# LPS25H_breakout.net
KiCad netlist of a schematic drawn in EAGLE
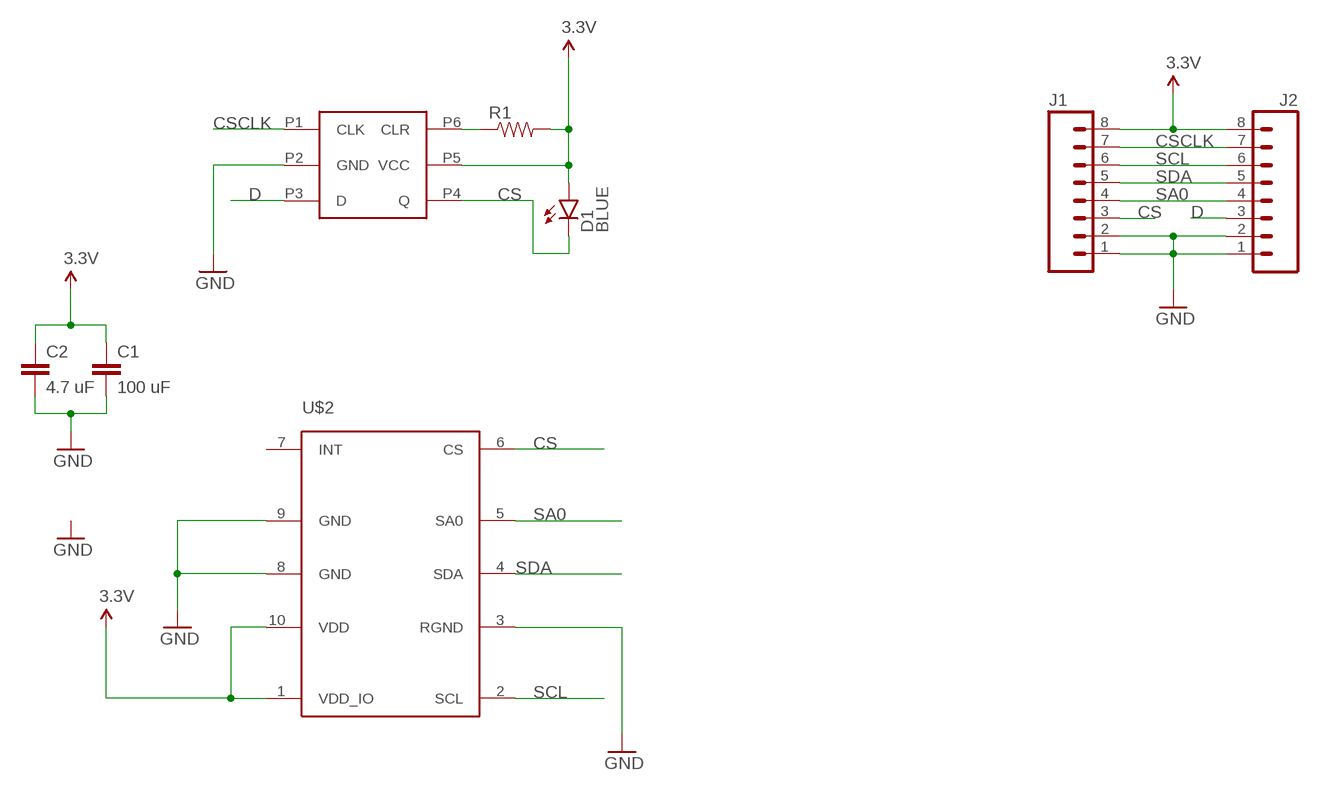
[diagram p0: schematic, sheet 1]

(export (version "E")
  (design (tool "Eeschema 10.0.6"))
  (components
    (comp (ref "C1")
      (value "100 uF")
      (footprint "eagle-import:0603-CAP")
      (libsource (lib "eagle-import") (part "CAP0603-CAP"))
    )
    (comp (ref "C2")
      (value "4.7 uF")
      (footprint "eagle-import:0603-CAP")
      (libsource (lib "eagle-import") (part "CAP0603-CAP"))
    )
    (comp (ref "D1")
      (value "BLUE")
      (footprint "eagle-import:LED-0603")
      (libsource (lib "eagle-import") (part "LED-BLUE0603"))
    )
    (comp (ref "J1")
      (value "M08BM08B-SRSS-TB")
      (footprint "eagle-import:BM08B-SRSS-TB")
      (libsource (lib "eagle-import") (part "M08BM08B-SRSS-TB"))
    )
    (comp (ref "J2")
      (value "M08BM08B-SRSS-TB")
      (footprint "eagle-import:BM08B-SRSS-TB")
      (libsource (lib "eagle-import") (part "M08BM08B-SRSS-TB"))
    )
    (comp (ref "R1")
      (value "RESISTOR0603-RES")
      (footprint "eagle-import:0603-RES")
      (libsource (lib "eagle-import") (part "RESISTOR0603-RES"))
    )
    (comp (ref "U$1")
      (value "SN74LVC1G175")
      (footprint "eagle-import:SN74LVC1G175")
      (libsource (lib "eagle-import") (part "SN74LVC1G175"))
    )
    (comp (ref "U$2")
      (value "LPS25H")
      (footprint "eagle-import:LPS25H")
      (libsource (lib "eagle-import") (part "LPS25H"))
    )
  )
  (nets
    (net (code "1") (name "/CS") (class "Default")
      (node (ref "D1") (pin "C") (pinfunction "C_C") (pintype "passive"))
      (node (ref "J1") (pin "3") (pinfunction "3_3") (pintype "passive"))
      (node (ref "U$1") (pin "P4") (pinfunction "Q_P4") (pintype "bidirectional"))
      (node (ref "U$2") (pin "6") (pinfunction "CS_6") (pintype "bidirectional"))
    )
    (net (code "2") (name "/CSCLK") (class "Default")
      (node (ref "J1") (pin "7") (pinfunction "7_7") (pintype "passive"))
      (node (ref "J2") (pin "7") (pinfunction "7_7") (pintype "passive"))
      (node (ref "U$1") (pin "P1") (pinfunction "CLK_P1") (pintype "bidirectional"))
    )
    (net (code "3") (name "/D") (class "Default")
      (node (ref "J2") (pin "3") (pinfunction "3_3") (pintype "passive"))
      (node (ref "U$1") (pin "P3") (pinfunction "D_P3") (pintype "bidirectional"))
    )
    (net (code "4") (name "/SA0") (class "Default")
      (node (ref "J1") (pin "4") (pinfunction "4_4") (pintype "passive"))
      (node (ref "J2") (pin "4") (pinfunction "4_4") (pintype "passive"))
      (node (ref "U$2") (pin "5") (pinfunction "SA0_5") (pintype "bidirectional"))
    )
    (net (code "5") (name "/SCL") (class "Default")
      (node (ref "J1") (pin "6") (pinfunction "6_6") (pintype "passive"))
      (node (ref "J2") (pin "6") (pinfunction "6_6") (pintype "passive"))
      (node (ref "U$2") (pin "2") (pinfunction "SCL_2") (pintype "bidirectional"))
    )
    (net (code "6") (name "/SDA") (class "Default")
      (node (ref "J1") (pin "5") (pinfunction "5_5") (pintype "passive"))
      (node (ref "J2") (pin "5") (pinfunction "5_5") (pintype "passive"))
      (node (ref "U$2") (pin "4") (pinfunction "SDA_4") (pintype "bidirectional"))
    )
    (net (code "7") (name "3.3V") (class "Default")
      (node (ref "C1") (pin "1") (pinfunction "1_1") (pintype "passive"))
      (node (ref "C2") (pin "1") (pinfunction "1_1") (pintype "passive"))
      (node (ref "D1") (pin "A") (pinfunction "A_A") (pintype "passive"))
      (node (ref "J1") (pin "8") (pinfunction "8_8") (pintype "passive"))
      (node (ref "J2") (pin "8") (pinfunction "8_8") (pintype "passive"))
      (node (ref "R1") (pin "2") (pinfunction "2_2") (pintype "passive"))
      (node (ref "U$1") (pin "P5") (pinfunction "VCC_P5") (pintype "bidirectional"))
      (node (ref "U$2") (pin "1") (pinfunction "VDD_IO_1") (pintype "power_in"))
      (node (ref "U$2") (pin "10") (pinfunction "VDD_10") (pintype "power_in"))
    )
    (net (code "8") (name "GND") (class "Default")
      (node (ref "C1") (pin "2") (pinfunction "2_2") (pintype "passive"))
      (node (ref "C2") (pin "2") (pinfunction "2_2") (pintype "passive"))
      (node (ref "J1") (pin "1") (pinfunction "1_1") (pintype "passive"))
      (node (ref "J1") (pin "2") (pinfunction "2_2") (pintype "passive"))
      (node (ref "J2") (pin "1") (pinfunction "1_1") (pintype "passive"))
      (node (ref "J2") (pin "2") (pinfunction "2_2") (pintype "passive"))
      (node (ref "U$1") (pin "P2") (pinfunction "GND_P2") (pintype "bidirectional"))
      (node (ref "U$2") (pin "3") (pinfunction "RGND_3") (pintype "bidirectional"))
      (node (ref "U$2") (pin "8") (pinfunction "GND_8") (pintype "power_in"))
      (node (ref "U$2") (pin "9") (pinfunction "GND_9") (pintype "power_in"))
    )
    (net (code "9") (name "Net-(U$1-CLR)") (class "Default")
      (node (ref "R1") (pin "1") (pinfunction "1_1") (pintype "passive"))
      (node (ref "U$1") (pin "P6") (pinfunction "CLR_P6") (pintype "bidirectional"))
    )
    (net (code "10") (name "unconnected-(U$2-INT-Pad7)") (class "Default")
      (node (ref "U$2") (pin "7") (pinfunction "INT_7") (pintype "bidirectional"))
    )
  )
)
